# RS485.net
KiCad netlist of a schematic drawn in Altium Designer
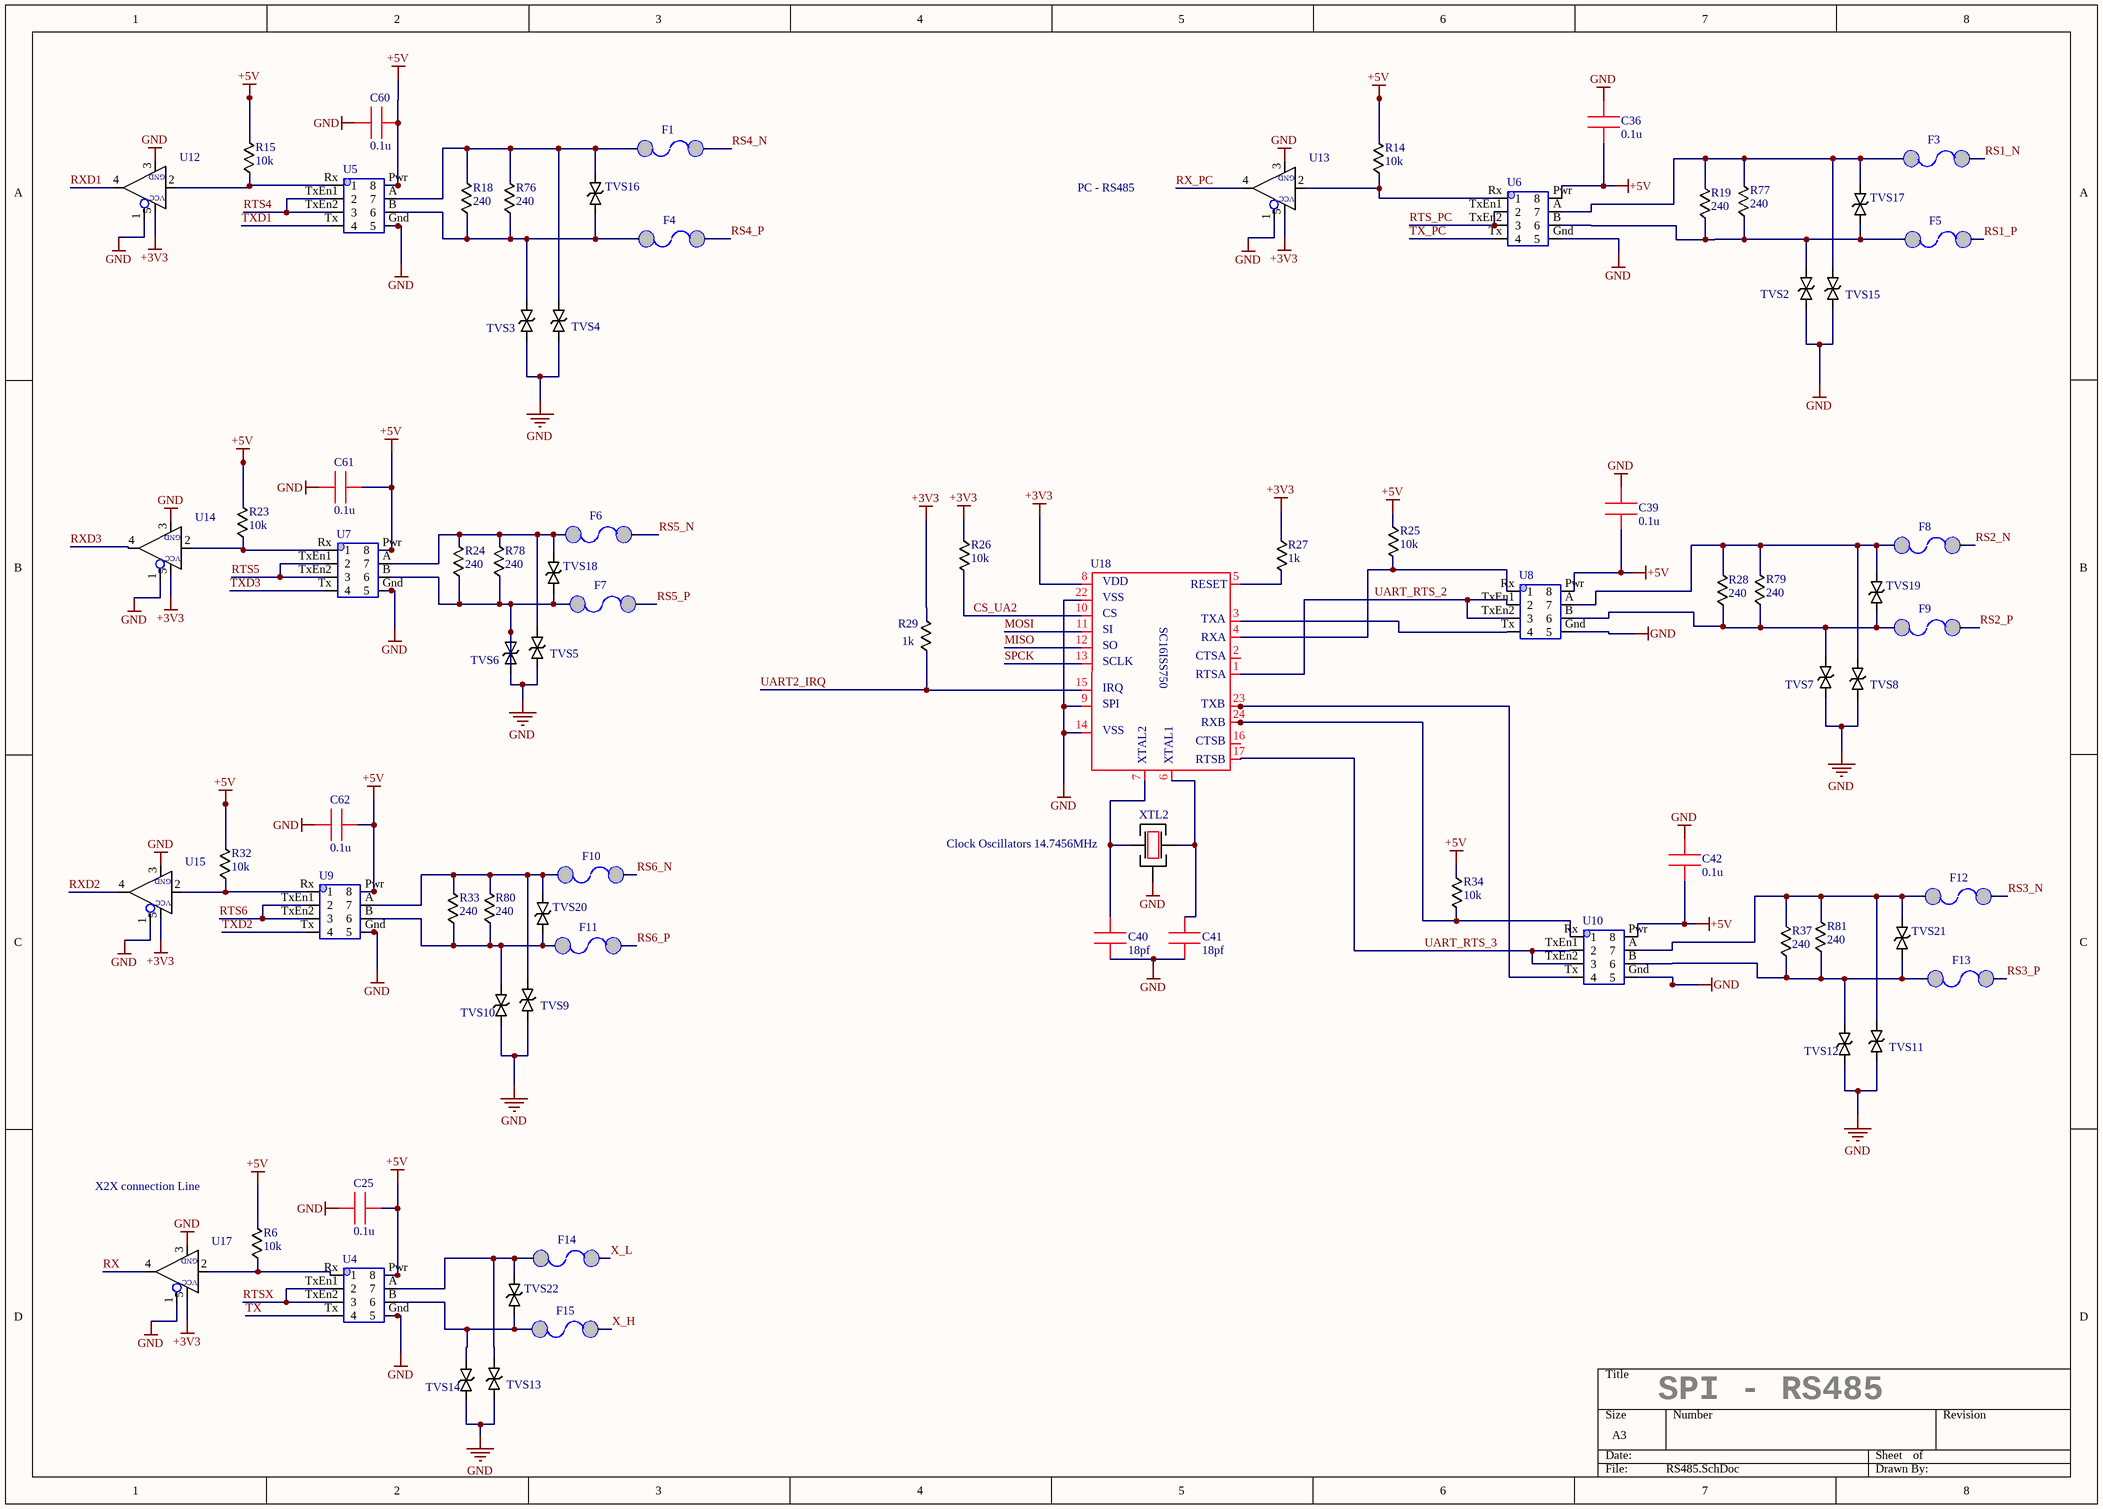
[diagram p0: RS485.SchDoc]

(export (version "E")
  (design (tool "Eeschema 10.0.6"))
  (components
    (comp (ref "C25")
      (value "0.1u")
      (footprint "0603")
      (fields (field (name "PART NUMBER") "GRM188R72A104KA35D"))
      (libsource (lib "kontr") (part "Capasitor 0805"))
    )
    (comp (ref "C36")
      (value "0.1u")
      (footprint "0603")
      (fields (field (name "PART NUMBER") "GRM188R72A104KA35D"))
      (libsource (lib "kontr") (part "Capasitor 0805"))
    )
    (comp (ref "C39")
      (value "0.1u")
      (footprint "0603")
      (fields (field (name "PART NUMBER") "GRM188R72A104KA35D"))
      (libsource (lib "kontr") (part "Capasitor 0805"))
    )
    (comp (ref "C40")
      (value "18pf")
      (footprint "0603")
      (fields (field (name "PART NUMBER") "GRM1885C1H180JA01D"))
      (libsource (lib "kontr") (part "Capasitor 0805"))
    )
    (comp (ref "C41")
      (value "18pf")
      (footprint "0603")
      (fields (field (name "PART NUMBER") "GRM1885C1H180JA01D"))
      (libsource (lib "kontr") (part "Capasitor 0805"))
    )
    (comp (ref "C42")
      (value "0.1u")
      (footprint "0603")
      (fields (field (name "PART NUMBER") "GRM188R72A104KA35D"))
      (libsource (lib "kontr") (part "Capasitor 0805"))
    )
    (comp (ref "C60")
      (value "0.1u")
      (footprint "0603")
      (fields (field (name "PART NUMBER") "GRM188R72A104KA35D"))
      (libsource (lib "kontr") (part "Capasitor 0805"))
    )
    (comp (ref "C61")
      (value "0.1u")
      (footprint "0603")
      (fields (field (name "PART NUMBER") "GRM188R72A104KA35D"))
      (libsource (lib "kontr") (part "Capasitor 0805"))
    )
    (comp (ref "C62")
      (value "0.1u")
      (footprint "0603")
      (fields (field (name "PART NUMBER") "GRM188R72A104KA35D"))
      (libsource (lib "kontr") (part "Capasitor 0805"))
    )
    (comp (ref "F1")
      (value "~")
      (footprint "1210")
      (fields (field (name "PART NUMBER") "MF-USMF005-2"))
      (libsource (lib "kontr") (part "Fuse PTS"))
    )
    (comp (ref "F3")
      (value "~")
      (footprint "1210")
      (fields (field (name "PART NUMBER") "MF-USMF005-2"))
      (libsource (lib "kontr") (part "Fuse PTS"))
    )
    (comp (ref "F4")
      (value "~")
      (footprint "1210")
      (fields (field (name "PART NUMBER") "MF-USMF005-2"))
      (libsource (lib "kontr") (part "Fuse PTS"))
    )
    (comp (ref "F5")
      (value "~")
      (footprint "1210")
      (fields (field (name "PART NUMBER") "MF-USMF005-2"))
      (libsource (lib "kontr") (part "Fuse PTS"))
    )
    (comp (ref "F6")
      (value "~")
      (footprint "1210")
      (fields (field (name "PART NUMBER") "MF-USMF005-2"))
      (libsource (lib "kontr") (part "Fuse PTS"))
    )
    (comp (ref "F7")
      (value "~")
      (footprint "1210")
      (fields (field (name "PART NUMBER") "MF-USMF005-2"))
      (libsource (lib "kontr") (part "Fuse PTS"))
    )
    (comp (ref "F8")
      (value "~")
      (footprint "1210")
      (fields (field (name "PART NUMBER") "MF-USMF005-2"))
      (libsource (lib "kontr") (part "Fuse PTS"))
    )
    (comp (ref "F9")
      (value "~")
      (footprint "1210")
      (fields (field (name "PART NUMBER") "MF-USMF005-2"))
      (libsource (lib "kontr") (part "Fuse PTS"))
    )
    (comp (ref "F10")
      (value "~")
      (footprint "1210")
      (fields (field (name "PART NUMBER") "MF-USMF005-2"))
      (libsource (lib "kontr") (part "Fuse PTS"))
    )
    (comp (ref "F11")
      (value "~")
      (footprint "1210")
      (fields (field (name "PART NUMBER") "MF-USMF005-2"))
      (libsource (lib "kontr") (part "Fuse PTS"))
    )
    (comp (ref "F12")
      (value "~")
      (footprint "1210")
      (fields (field (name "PART NUMBER") "MF-USMF005-2"))
      (libsource (lib "kontr") (part "Fuse PTS"))
    )
    (comp (ref "F13")
      (value "~")
      (footprint "1210")
      (fields (field (name "PART NUMBER") "MF-USMF005-2"))
      (libsource (lib "kontr") (part "Fuse PTS"))
    )
    (comp (ref "F14")
      (value "~")
      (footprint "1210")
      (fields (field (name "PART NUMBER") "MF-USMF005-2"))
      (libsource (lib "kontr") (part "Fuse PTS"))
    )
    (comp (ref "F15")
      (value "~")
      (footprint "1210")
      (fields (field (name "PART NUMBER") "MF-USMF005-2"))
      (libsource (lib "kontr") (part "Fuse PTS"))
    )
    (comp (ref "R6")
      (value "10k")
      (footprint "0603")
      (fields (field (name "PART NUMBER") "RC0603JR-0710K"))
      (libsource (lib "kontr") (part "Resistor 0805"))
    )
    (comp (ref "R14")
      (value "10k")
      (footprint "0603")
      (fields (field (name "PART NUMBER") "RC0603JR-0710K"))
      (libsource (lib "kontr") (part "Resistor 0805"))
    )
    (comp (ref "R15")
      (value "10k")
      (footprint "0603")
      (fields (field (name "PART NUMBER") "RC0603JR-0710K"))
      (libsource (lib "kontr") (part "Resistor 0805"))
    )
    (comp (ref "R18")
      (value "240")
      (footprint "0603")
      (fields (field (name "PART NUMBER") "RC0603FR-07240RL"))
      (libsource (lib "kontr") (part "Resistor 0805"))
    )
    (comp (ref "R19")
      (value "240")
      (footprint "0603")
      (fields (field (name "PART NUMBER") "RC0603FR-07240RL"))
      (libsource (lib "kontr") (part "Resistor 0805"))
    )
    (comp (ref "R23")
      (value "10k")
      (footprint "0603")
      (fields (field (name "PART NUMBER") "RC0603JR-0710K"))
      (libsource (lib "kontr") (part "Resistor 0805"))
    )
    (comp (ref "R24")
      (value "240")
      (footprint "0603")
      (fields (field (name "PART NUMBER") "RC0603FR-07240RL"))
      (libsource (lib "kontr") (part "Resistor 0805"))
    )
    (comp (ref "R25")
      (value "10k")
      (footprint "0603")
      (fields (field (name "PART NUMBER") "RC0603JR-0710K"))
      (libsource (lib "kontr") (part "Resistor 0805"))
    )
    (comp (ref "R26")
      (value "10k")
      (footprint "0603")
      (fields (field (name "PART NUMBER") "RC0603JR-0710K"))
      (libsource (lib "kontr") (part "Resistor 0805"))
    )
    (comp (ref "R27")
      (value "1k")
      (footprint "0603")
      (fields (field (name "PART NUMBER") "RC0603JR-071KL"))
      (libsource (lib "kontr") (part "Resistor 0805"))
    )
    (comp (ref "R28")
      (value "240")
      (footprint "0603")
      (fields (field (name "PART NUMBER") "RC0603FR-07240RL"))
      (libsource (lib "kontr") (part "Resistor 0805"))
    )
    (comp (ref "R29")
      (value "1k")
      (footprint "0603")
      (fields (field (name "PART NUMBER") "RC0603JR-071KL"))
      (libsource (lib "kontr") (part "Resistor 0805"))
    )
    (comp (ref "R32")
      (value "10k")
      (footprint "0603")
      (fields (field (name "PART NUMBER") "RC0603JR-0710K"))
      (libsource (lib "kontr") (part "Resistor 0805"))
    )
    (comp (ref "R33")
      (value "240")
      (footprint "0603")
      (fields (field (name "PART NUMBER") "RC0603FR-07240RL"))
      (libsource (lib "kontr") (part "Resistor 0805"))
    )
    (comp (ref "R34")
      (value "10k")
      (footprint "0603")
      (fields (field (name "PART NUMBER") "RC0603JR-0710K"))
      (libsource (lib "kontr") (part "Resistor 0805"))
    )
    (comp (ref "R37")
      (value "240")
      (footprint "0603")
      (fields (field (name "PART NUMBER") "RC0603FR-07240RL"))
      (libsource (lib "kontr") (part "Resistor 0805"))
    )
    (comp (ref "R76")
      (value "240")
      (footprint "0603")
      (fields (field (name "PART NUMBER") "RC0603FR-07240RL"))
      (libsource (lib "kontr") (part "Resistor 0805"))
    )
    (comp (ref "R77")
      (value "240")
      (footprint "0603")
      (fields (field (name "PART NUMBER") "RC0603FR-07240RL"))
      (libsource (lib "kontr") (part "Resistor 0805"))
    )
    (comp (ref "R78")
      (value "240")
      (footprint "0603")
      (fields (field (name "PART NUMBER") "RC0603FR-07240RL"))
      (libsource (lib "kontr") (part "Resistor 0805"))
    )
    (comp (ref "R79")
      (value "240")
      (footprint "0603")
      (fields (field (name "PART NUMBER") "RC0603FR-07240RL"))
      (libsource (lib "kontr") (part "Resistor 0805"))
    )
    (comp (ref "R80")
      (value "240")
      (footprint "0603")
      (fields (field (name "PART NUMBER") "RC0603FR-07240RL"))
      (libsource (lib "kontr") (part "Resistor 0805"))
    )
    (comp (ref "R81")
      (value "240")
      (footprint "0603")
      (fields (field (name "PART NUMBER") "RC0603FR-07240RL"))
      (libsource (lib "kontr") (part "Resistor 0805"))
    )
    (comp (ref "TVS2")
      (value "~")
      (footprint "DO-214AC")
      (fields (field (name "PART NUMBER") "SMAJ5.0CA"))
      (libsource (lib "kontr") (part "SMAJ5.0CA"))
    )
    (comp (ref "TVS3")
      (value "~")
      (footprint "DO-214AC")
      (fields (field (name "PART NUMBER") "SMAJ5.0CA"))
      (libsource (lib "kontr") (part "SMAJ5.0CA"))
    )
    (comp (ref "TVS4")
      (value "~")
      (footprint "DO-214AC")
      (fields (field (name "PART NUMBER") "SMAJ5.0CA"))
      (libsource (lib "kontr") (part "SMAJ5.0CA"))
    )
    (comp (ref "TVS5")
      (value "~")
      (footprint "DO-214AC")
      (fields (field (name "PART NUMBER") "SMAJ5.0CA"))
      (libsource (lib "kontr") (part "SMAJ5.0CA"))
    )
    (comp (ref "TVS6")
      (value "~")
      (footprint "DO-214AC")
      (fields (field (name "PART NUMBER") "SMAJ5.0CA"))
      (libsource (lib "kontr") (part "SMAJ5.0CA"))
    )
    (comp (ref "TVS7")
      (value "~")
      (footprint "DO-214AC")
      (fields (field (name "PART NUMBER") "SMAJ5.0CA"))
      (libsource (lib "kontr") (part "SMAJ5.0CA"))
    )
    (comp (ref "TVS8")
      (value "~")
      (footprint "DO-214AC")
      (fields (field (name "PART NUMBER") "SMAJ5.0CA"))
      (libsource (lib "kontr") (part "SMAJ5.0CA"))
    )
    (comp (ref "TVS9")
      (value "~")
      (footprint "DO-214AC")
      (fields (field (name "PART NUMBER") "SMAJ5.0CA"))
      (libsource (lib "kontr") (part "SMAJ5.0CA"))
    )
    (comp (ref "TVS10")
      (value "~")
      (footprint "DO-214AC")
      (fields (field (name "PART NUMBER") "SMAJ5.0CA"))
      (libsource (lib "kontr") (part "SMAJ5.0CA"))
    )
    (comp (ref "TVS11")
      (value "~")
      (footprint "DO-214AC")
      (fields (field (name "PART NUMBER") "SMAJ5.0CA"))
      (libsource (lib "kontr") (part "SMAJ5.0CA"))
    )
    (comp (ref "TVS12")
      (value "~")
      (footprint "DO-214AC")
      (fields (field (name "PART NUMBER") "SMAJ5.0CA"))
      (libsource (lib "kontr") (part "SMAJ5.0CA"))
    )
    (comp (ref "TVS13")
      (value "~")
      (footprint "DO-214AC")
      (fields (field (name "PART NUMBER") "SMAJ5.0CA"))
      (libsource (lib "kontr") (part "SMAJ5.0CA"))
    )
    (comp (ref "TVS14")
      (value "~")
      (footprint "DO-214AC")
      (fields (field (name "PART NUMBER") "SMAJ5.0CA"))
      (libsource (lib "kontr") (part "SMAJ5.0CA"))
    )
    (comp (ref "TVS15")
      (value "~")
      (footprint "DO-214AC")
      (fields (field (name "PART NUMBER") "SMAJ5.0CA"))
      (libsource (lib "kontr") (part "SMAJ5.0CA"))
    )
    (comp (ref "TVS16")
      (value "~")
      (footprint "DO-214AC")
      (fields (field (name "PART NUMBER") "SMAJ5.0CA"))
      (libsource (lib "kontr") (part "TVS"))
    )
    (comp (ref "TVS17")
      (value "~")
      (footprint "DO-214AC")
      (fields (field (name "PART NUMBER") "SMAJ5.0CA"))
      (libsource (lib "kontr") (part "TVS"))
    )
    (comp (ref "TVS18")
      (value "~")
      (footprint "DO-214AC")
      (fields (field (name "PART NUMBER") "SMAJ5.0CA"))
      (libsource (lib "kontr") (part "TVS"))
    )
    (comp (ref "TVS19")
      (value "~")
      (footprint "DO-214AC")
      (fields (field (name "PART NUMBER") "SMAJ5.0CA"))
      (libsource (lib "kontr") (part "TVS"))
    )
    (comp (ref "TVS20")
      (value "~")
      (footprint "DO-214AC")
      (fields (field (name "PART NUMBER") "SMAJ5.0CA"))
      (libsource (lib "kontr") (part "TVS"))
    )
    (comp (ref "TVS21")
      (value "~")
      (footprint "DO-214AC")
      (fields (field (name "PART NUMBER") "SMAJ5.0CA"))
      (libsource (lib "kontr") (part "TVS"))
    )
    (comp (ref "TVS22")
      (value "~")
      (footprint "DO-214AC")
      (fields (field (name "PART NUMBER") "SMAJ5.0CA"))
      (libsource (lib "kontr") (part "TVS"))
    )
    (comp (ref "U4")
      (value "~")
      (footprint "MAX485 - duplicate")
      (fields (field (name "PART NUMBER") "SN65HVD3082EDR"))
      (libsource (lib "Schlib1") (part "MAX485"))
    )
    (comp (ref "U5")
      (value "~")
      (footprint "MAX485 - duplicate")
      (fields (field (name "PART NUMBER") "SN65HVD3082EDR"))
      (libsource (lib "Schlib1") (part "MAX485"))
    )
    (comp (ref "U6")
      (value "~")
      (footprint "MAX485 - duplicate")
      (fields (field (name "PART NUMBER") "SN65HVD3082EDR"))
      (libsource (lib "Schlib1") (part "MAX485"))
    )
    (comp (ref "U7")
      (value "~")
      (footprint "MAX485 - duplicate")
      (fields (field (name "PART NUMBER") "SN65HVD3082EDR"))
      (libsource (lib "Schlib1") (part "MAX485"))
    )
    (comp (ref "U8")
      (value "~")
      (footprint "MAX485 - duplicate")
      (fields (field (name "PART NUMBER") "SN65HVD3082EDR"))
      (libsource (lib "Schlib1") (part "MAX485"))
    )
    (comp (ref "U9")
      (value "~")
      (footprint "MAX485 - duplicate")
      (fields (field (name "PART NUMBER") "SN65HVD3082EDR"))
      (libsource (lib "Schlib1") (part "MAX485"))
    )
    (comp (ref "U10")
      (value "~")
      (footprint "MAX485 - duplicate")
      (fields (field (name "PART NUMBER") "SN65HVD3082EDR"))
      (libsource (lib "Schlib1") (part "MAX485"))
    )
    (comp (ref "U12")
      (value "~")
      (footprint "SOT23 - 5 lead")
      (fields (field (name "PART NUMBER") "SN74LVC1G125DBVR"))
      (libsource (lib "kontr") (part "Gate"))
    )
    (comp (ref "U13")
      (value "~")
      (footprint "SOT23 - 5 lead")
      (fields (field (name "PART NUMBER") "SN74LVC1G125DBVR"))
      (libsource (lib "kontr") (part "Gate"))
    )
    (comp (ref "U14")
      (value "~")
      (footprint "SOT23 - 5 lead")
      (fields (field (name "PART NUMBER") "SN74LVC1G125DBVR"))
      (libsource (lib "kontr") (part "Gate"))
    )
    (comp (ref "U15")
      (value "~")
      (footprint "SOT23 - 5 lead")
      (fields (field (name "PART NUMBER") "SN74LVC1G125DBVR"))
      (libsource (lib "kontr") (part "Gate"))
    )
    (comp (ref "U17")
      (value "~")
      (footprint "SOT23 - 5 lead")
      (fields (field (name "PART NUMBER") "SN74LVC1G125DBVR"))
      (libsource (lib "kontr") (part "Gate"))
    )
    (comp (ref "U18")
      (value "~")
      (footprint "TSSOP28")
      (fields (field (name "PART NUMBER") "SC16IS752IPW,128"))
      (libsource (lib "kontr") (part "SC16IS752"))
    )
    (comp (ref "XTL2")
      (value "~")
      (footprint "KX-7 XTAL")
      (fields
        (field (name "PART DESCRIPTION") "Clock Oscillators 14.7456MHz")
        (field (name "PART NUMBER") "Geyer KX-7 14.7456MHz")
      )
      (libsource (lib "kontr") (part "KX-7"))
    )
  )
  (nets
    (net (code "1") (name "+3V3") (class "Default")
      (node (ref "R26") (pin "1") (pintype "passive"))
      (node (ref "R27") (pin "1") (pintype "passive"))
      (node (ref "R29") (pin "2") (pintype "passive"))
      (node (ref "U12") (pin "5") (pinfunction "7_5") (pintype "passive"))
      (node (ref "U13") (pin "5") (pinfunction "7_5") (pintype "passive"))
      (node (ref "U14") (pin "5") (pinfunction "7_5") (pintype "passive"))
      (node (ref "U15") (pin "5") (pinfunction "7_5") (pintype "passive"))
      (node (ref "U17") (pin "5") (pinfunction "7_5") (pintype "passive"))
      (node (ref "U18") (pin "8") (pinfunction "8_8") (pintype "passive"))
    )
    (net (code "2") (name "+5V") (class "Default")
      (node (ref "C25") (pin "2") (pinfunction "2_2") (pintype "passive"))
      (node (ref "C36") (pin "2") (pinfunction "2_2") (pintype "passive"))
      (node (ref "C39") (pin "2") (pinfunction "2_2") (pintype "passive"))
      (node (ref "C42") (pin "2") (pinfunction "2_2") (pintype "passive"))
      (node (ref "C60") (pin "2") (pinfunction "2_2") (pintype "passive"))
      (node (ref "C61") (pin "2") (pinfunction "2_2") (pintype "passive"))
      (node (ref "C62") (pin "2") (pinfunction "2_2") (pintype "passive"))
      (node (ref "R14") (pin "2") (pintype "passive"))
      (node (ref "R15") (pin "2") (pintype "passive"))
      (node (ref "R23") (pin "2") (pintype "passive"))
      (node (ref "R25") (pin "1") (pintype "passive"))
      (node (ref "R32") (pin "2") (pintype "passive"))
      (node (ref "R34") (pin "1") (pintype "passive"))
      (node (ref "R6") (pin "2") (pintype "passive"))
      (node (ref "U10") (pin "Pwr") (pinfunction "8_Pwr") (pintype "passive"))
      (node (ref "U4") (pin "Pwr") (pinfunction "8_Pwr") (pintype "passive"))
      (node (ref "U5") (pin "Pwr") (pinfunction "8_Pwr") (pintype "passive"))
      (node (ref "U6") (pin "Pwr") (pinfunction "8_Pwr") (pintype "passive"))
      (node (ref "U7") (pin "Pwr") (pinfunction "8_Pwr") (pintype "passive"))
      (node (ref "U8") (pin "Pwr") (pinfunction "8_Pwr") (pintype "passive"))
      (node (ref "U9") (pin "Pwr") (pinfunction "8_Pwr") (pintype "passive"))
    )
    (net (code "3") (name "/CS_UA2") (class "Default")
      (node (ref "R26") (pin "2") (pintype "passive"))
      (node (ref "U18") (pin "10") (pinfunction "10_10") (pintype "passive"))
    )
    (net (code "4") (name "/MISO") (class "Default")
      (node (ref "U18") (pin "12") (pinfunction "12_12") (pintype "passive"))
    )
    (net (code "5") (name "/MOSI") (class "Default")
      (node (ref "U18") (pin "11") (pinfunction "11_11") (pintype "passive"))
    )
    (net (code "6") (name "/RS1_N") (class "Default")
      (node (ref "F3") (pin "1") (pinfunction "1_1") (pintype "passive"))
    )
    (net (code "7") (name "/RS1_P") (class "Default")
      (node (ref "F5") (pin "1") (pinfunction "1_1") (pintype "passive"))
    )
    (net (code "8") (name "/RS2_N") (class "Default")
      (node (ref "F8") (pin "1") (pinfunction "1_1") (pintype "passive"))
    )
    (net (code "9") (name "/RS2_P") (class "Default")
      (node (ref "F9") (pin "1") (pinfunction "1_1") (pintype "passive"))
    )
    (net (code "10") (name "/RS3_N") (class "Default")
      (node (ref "F12") (pin "1") (pinfunction "1_1") (pintype "passive"))
    )
    (net (code "11") (name "/RS3_P") (class "Default")
      (node (ref "F13") (pin "1") (pinfunction "1_1") (pintype "passive"))
    )
    (net (code "12") (name "/RS4_N") (class "Default")
      (node (ref "F1") (pin "1") (pinfunction "1_1") (pintype "passive"))
    )
    (net (code "13") (name "/RS4_P") (class "Default")
      (node (ref "F4") (pin "1") (pinfunction "1_1") (pintype "passive"))
    )
    (net (code "14") (name "/RS5_N") (class "Default")
      (node (ref "F6") (pin "1") (pinfunction "1_1") (pintype "passive"))
    )
    (net (code "15") (name "/RS5_P") (class "Default")
      (node (ref "F7") (pin "1") (pinfunction "1_1") (pintype "passive"))
    )
    (net (code "16") (name "/RS6_N") (class "Default")
      (node (ref "F10") (pin "1") (pinfunction "1_1") (pintype "passive"))
    )
    (net (code "17") (name "/RS6_P") (class "Default")
      (node (ref "F11") (pin "1") (pinfunction "1_1") (pintype "passive"))
    )
    (net (code "18") (name "/RTS4") (class "Default")
      (node (ref "U5") (pin "TxEn1") (pinfunction "2_TxEn1") (pintype "passive"))
      (node (ref "U5") (pin "TxEn2") (pinfunction "3_TxEn2") (pintype "passive"))
    )
    (net (code "19") (name "/RTS5") (class "Default")
      (node (ref "U7") (pin "TxEn1") (pinfunction "2_TxEn1") (pintype "passive"))
      (node (ref "U7") (pin "TxEn2") (pinfunction "3_TxEn2") (pintype "passive"))
    )
    (net (code "20") (name "/RTS6") (class "Default")
      (node (ref "U9") (pin "TxEn1") (pinfunction "2_TxEn1") (pintype "passive"))
      (node (ref "U9") (pin "TxEn2") (pinfunction "3_TxEn2") (pintype "passive"))
    )
    (net (code "21") (name "/RTSX") (class "Default")
      (node (ref "U4") (pin "TxEn1") (pinfunction "2_TxEn1") (pintype "passive"))
      (node (ref "U4") (pin "TxEn2") (pinfunction "3_TxEn2") (pintype "passive"))
    )
    (net (code "22") (name "/RTS_PC") (class "Default")
      (node (ref "U6") (pin "TxEn1") (pinfunction "2_TxEn1") (pintype "passive"))
      (node (ref "U6") (pin "TxEn2") (pinfunction "3_TxEn2") (pintype "passive"))
    )
    (net (code "23") (name "/RX") (class "Default")
      (node (ref "U17") (pin "4") (pinfunction "7_4") (pintype "passive"))
    )
    (net (code "24") (name "/RXD1") (class "Default")
      (node (ref "U12") (pin "4") (pinfunction "7_4") (pintype "passive"))
    )
    (net (code "25") (name "/RXD2") (class "Default")
      (node (ref "U15") (pin "4") (pinfunction "7_4") (pintype "passive"))
    )
    (net (code "26") (name "/RXD3") (class "Default")
      (node (ref "U14") (pin "4") (pinfunction "7_4") (pintype "passive"))
    )
    (net (code "27") (name "/RX_PC") (class "Default")
      (node (ref "U13") (pin "4") (pinfunction "7_4") (pintype "passive"))
    )
    (net (code "28") (name "/SPCK") (class "Default")
      (node (ref "U18") (pin "13") (pinfunction "13_13") (pintype "passive"))
    )
    (net (code "29") (name "/TX") (class "Default")
      (node (ref "U4") (pin "Tx") (pinfunction "4_Tx") (pintype "passive"))
    )
    (net (code "30") (name "/TXD1") (class "Default")
      (node (ref "U5") (pin "Tx") (pinfunction "4_Tx") (pintype "passive"))
    )
    (net (code "31") (name "/TXD2") (class "Default")
      (node (ref "U9") (pin "Tx") (pinfunction "4_Tx") (pintype "passive"))
    )
    (net (code "32") (name "/TXD3") (class "Default")
      (node (ref "U7") (pin "Tx") (pinfunction "4_Tx") (pintype "passive"))
    )
    (net (code "33") (name "/TX_PC") (class "Default")
      (node (ref "U6") (pin "Tx") (pinfunction "4_Tx") (pintype "passive"))
    )
    (net (code "34") (name "/UART2_IRQ") (class "Default")
      (node (ref "R29") (pin "1") (pintype "passive"))
      (node (ref "U18") (pin "15") (pinfunction "15_15") (pintype "passive"))
    )
    (net (code "35") (name "/UART_RTS_2") (class "Default")
      (node (ref "U18") (pin "1") (pinfunction "1_1") (pintype "passive"))
      (node (ref "U8") (pin "TxEn1") (pinfunction "2_TxEn1") (pintype "passive"))
      (node (ref "U8") (pin "TxEn2") (pinfunction "3_TxEn2") (pintype "passive"))
    )
    (net (code "36") (name "/UART_RTS_3") (class "Default")
      (node (ref "U10") (pin "TxEn1") (pinfunction "2_TxEn1") (pintype "passive"))
      (node (ref "U10") (pin "TxEn2") (pinfunction "3_TxEn2") (pintype "passive"))
      (node (ref "U18") (pin "17") (pinfunction "17_17") (pintype "passive"))
    )
    (net (code "37") (name "/X_H") (class "Default")
      (node (ref "F15") (pin "1") (pinfunction "1_1") (pintype "passive"))
    )
    (net (code "38") (name "/X_L") (class "Default")
      (node (ref "F14") (pin "1") (pinfunction "1_1") (pintype "passive"))
    )
    (net (code "39") (name "GND") (class "Default")
      (node (ref "C25") (pin "1") (pinfunction "1_1") (pintype "passive"))
      (node (ref "C36") (pin "1") (pinfunction "1_1") (pintype "passive"))
      (node (ref "C39") (pin "1") (pinfunction "1_1") (pintype "passive"))
      (node (ref "C40") (pin "1") (pinfunction "1_1") (pintype "passive"))
      (node (ref "C41") (pin "1") (pinfunction "1_1") (pintype "passive"))
      (node (ref "C42") (pin "1") (pinfunction "1_1") (pintype "passive"))
      (node (ref "C60") (pin "1") (pinfunction "1_1") (pintype "passive"))
      (node (ref "C61") (pin "1") (pinfunction "1_1") (pintype "passive"))
      (node (ref "C62") (pin "1") (pinfunction "1_1") (pintype "passive"))
      (node (ref "TVS10") (pin "1") (pinfunction "1_1") (pintype "passive"))
      (node (ref "TVS11") (pin "1") (pinfunction "1_1") (pintype "passive"))
      (node (ref "TVS12") (pin "1") (pinfunction "1_1") (pintype "passive"))
      (node (ref "TVS13") (pin "1") (pinfunction "1_1") (pintype "passive"))
      (node (ref "TVS14") (pin "1") (pinfunction "1_1") (pintype "passive"))
      (node (ref "TVS15") (pin "1") (pinfunction "1_1") (pintype "passive"))
      (node (ref "TVS2") (pin "1") (pinfunction "1_1") (pintype "passive"))
      (node (ref "TVS3") (pin "1") (pinfunction "1_1") (pintype "passive"))
      (node (ref "TVS4") (pin "1") (pinfunction "1_1") (pintype "passive"))
      (node (ref "TVS5") (pin "1") (pinfunction "1_1") (pintype "passive"))
      (node (ref "TVS6") (pin "1") (pinfunction "1_1") (pintype "passive"))
      (node (ref "TVS7") (pin "1") (pinfunction "1_1") (pintype "passive"))
      (node (ref "TVS8") (pin "1") (pinfunction "1_1") (pintype "passive"))
      (node (ref "TVS9") (pin "1") (pinfunction "1_1") (pintype "passive"))
      (node (ref "U10") (pin "Gnd") (pinfunction "5_Gnd") (pintype "passive"))
      (node (ref "U12") (pin "1") (pinfunction "7_1") (pintype "passive"))
      (node (ref "U12") (pin "3") (pinfunction "7_3") (pintype "passive"))
      (node (ref "U13") (pin "1") (pinfunction "7_1") (pintype "passive"))
      (node (ref "U13") (pin "3") (pinfunction "7_3") (pintype "passive"))
      (node (ref "U14") (pin "1") (pinfunction "7_1") (pintype "passive"))
      (node (ref "U14") (pin "3") (pinfunction "7_3") (pintype "passive"))
      (node (ref "U15") (pin "1") (pinfunction "7_1") (pintype "passive"))
      (node (ref "U15") (pin "3") (pinfunction "7_3") (pintype "passive"))
      (node (ref "U17") (pin "1") (pinfunction "7_1") (pintype "passive"))
      (node (ref "U17") (pin "3") (pinfunction "7_3") (pintype "passive"))
      (node (ref "U18") (pin "14") (pinfunction "14_14") (pintype "passive"))
      (node (ref "U18") (pin "22") (pinfunction "22_22") (pintype "passive"))
      (node (ref "U18") (pin "9") (pinfunction "9_9") (pintype "passive"))
      (node (ref "U4") (pin "Gnd") (pinfunction "5_Gnd") (pintype "passive"))
      (node (ref "U5") (pin "Gnd") (pinfunction "5_Gnd") (pintype "passive"))
      (node (ref "U6") (pin "Gnd") (pinfunction "5_Gnd") (pintype "passive"))
      (node (ref "U7") (pin "Gnd") (pinfunction "5_Gnd") (pintype "passive"))
      (node (ref "U8") (pin "Gnd") (pinfunction "5_Gnd") (pintype "passive"))
      (node (ref "U9") (pin "Gnd") (pinfunction "5_Gnd") (pintype "passive"))
      (node (ref "XTL2") (pin "2") (pinfunction "2_2") (pintype "passive"))
    )
    (net (code "40") (name "Net-(C40-Pad2)") (class "Default")
      (node (ref "C40") (pin "2") (pinfunction "2_2") (pintype "passive"))
      (node (ref "U18") (pin "7") (pinfunction "7_7") (pintype "passive"))
      (node (ref "XTL2") (pin "1") (pinfunction "5_1") (pintype "passive"))
    )
    (net (code "41") (name "Net-(C41-Pad2)") (class "Default")
      (node (ref "C41") (pin "2") (pinfunction "2_2") (pintype "passive"))
      (node (ref "U18") (pin "6") (pinfunction "6_6") (pintype "passive"))
      (node (ref "XTL2") (pin "3") (pinfunction "5_3") (pintype "passive"))
    )
    (net (code "42") (name "Net-(R27-Pad2)") (class "Default")
      (node (ref "R27") (pin "2") (pintype "passive"))
      (node (ref "U18") (pin "5") (pinfunction "5_5") (pintype "passive"))
    )
    (net (code "43") (name "Net-(U4-1)") (class "Default")
      (node (ref "R6") (pin "1") (pintype "passive"))
      (node (ref "U17") (pin "2") (pinfunction "7_2") (pintype "passive"))
      (node (ref "U4") (pin "Rx") (pinfunction "1_Rx") (pintype "passive"))
    )
    (net (code "44") (name "Net-(U4-6)") (class "Default")
      (node (ref "F15") (pin "2") (pinfunction "2_2") (pintype "passive"))
      (node (ref "TVS14") (pin "2") (pinfunction "2_2") (pintype "passive"))
      (node (ref "TVS22") (pin "1") (pinfunction "1_1") (pintype "passive"))
      (node (ref "U4") (pin "B") (pinfunction "6_B") (pintype "passive"))
    )
    (net (code "45") (name "Net-(U4-7)") (class "Default")
      (node (ref "F14") (pin "2") (pinfunction "2_2") (pintype "passive"))
      (node (ref "TVS13") (pin "2") (pinfunction "2_2") (pintype "passive"))
      (node (ref "TVS22") (pin "2") (pinfunction "2_2") (pintype "passive"))
      (node (ref "U4") (pin "A") (pinfunction "7_A") (pintype "passive"))
    )
    (net (code "46") (name "Net-(U5-1)") (class "Default")
      (node (ref "R15") (pin "1") (pintype "passive"))
      (node (ref "U12") (pin "2") (pinfunction "7_2") (pintype "passive"))
      (node (ref "U5") (pin "Rx") (pinfunction "1_Rx") (pintype "passive"))
    )
    (net (code "47") (name "Net-(U5-6)") (class "Default")
      (node (ref "F4") (pin "2") (pinfunction "2_2") (pintype "passive"))
      (node (ref "R18") (pin "1") (pintype "passive"))
      (node (ref "R76") (pin "1") (pintype "passive"))
      (node (ref "TVS16") (pin "1") (pinfunction "1_1") (pintype "passive"))
      (node (ref "TVS3") (pin "2") (pinfunction "2_2") (pintype "passive"))
      (node (ref "U5") (pin "B") (pinfunction "6_B") (pintype "passive"))
    )
    (net (code "48") (name "Net-(U5-7)") (class "Default")
      (node (ref "F1") (pin "2") (pinfunction "2_2") (pintype "passive"))
      (node (ref "R18") (pin "2") (pintype "passive"))
      (node (ref "R76") (pin "2") (pintype "passive"))
      (node (ref "TVS16") (pin "2") (pinfunction "2_2") (pintype "passive"))
      (node (ref "TVS4") (pin "2") (pinfunction "2_2") (pintype "passive"))
      (node (ref "U5") (pin "A") (pinfunction "7_A") (pintype "passive"))
    )
    (net (code "49") (name "Net-(U6-1)") (class "Default")
      (node (ref "R14") (pin "1") (pintype "passive"))
      (node (ref "U13") (pin "2") (pinfunction "7_2") (pintype "passive"))
      (node (ref "U6") (pin "Rx") (pinfunction "1_Rx") (pintype "passive"))
    )
    (net (code "50") (name "Net-(U6-6)") (class "Default")
      (node (ref "F5") (pin "2") (pinfunction "2_2") (pintype "passive"))
      (node (ref "R19") (pin "1") (pintype "passive"))
      (node (ref "R77") (pin "1") (pintype "passive"))
      (node (ref "TVS17") (pin "1") (pinfunction "1_1") (pintype "passive"))
      (node (ref "TVS2") (pin "2") (pinfunction "2_2") (pintype "passive"))
      (node (ref "U6") (pin "B") (pinfunction "6_B") (pintype "passive"))
    )
    (net (code "51") (name "Net-(U6-7)") (class "Default")
      (node (ref "F3") (pin "2") (pinfunction "2_2") (pintype "passive"))
      (node (ref "R19") (pin "2") (pintype "passive"))
      (node (ref "R77") (pin "2") (pintype "passive"))
      (node (ref "TVS15") (pin "2") (pinfunction "2_2") (pintype "passive"))
      (node (ref "TVS17") (pin "2") (pinfunction "2_2") (pintype "passive"))
      (node (ref "U6") (pin "A") (pinfunction "7_A") (pintype "passive"))
    )
    (net (code "52") (name "Net-(U7-1)") (class "Default")
      (node (ref "R23") (pin "1") (pintype "passive"))
      (node (ref "U14") (pin "2") (pinfunction "7_2") (pintype "passive"))
      (node (ref "U7") (pin "Rx") (pinfunction "1_Rx") (pintype "passive"))
    )
    (net (code "53") (name "Net-(U7-6)") (class "Default")
      (node (ref "F7") (pin "2") (pinfunction "2_2") (pintype "passive"))
      (node (ref "R24") (pin "1") (pintype "passive"))
      (node (ref "R78") (pin "1") (pintype "passive"))
      (node (ref "TVS18") (pin "1") (pinfunction "1_1") (pintype "passive"))
      (node (ref "TVS6") (pin "2") (pinfunction "2_2") (pintype "passive"))
      (node (ref "U7") (pin "B") (pinfunction "6_B") (pintype "passive"))
    )
    (net (code "54") (name "Net-(U7-7)") (class "Default")
      (node (ref "F6") (pin "2") (pinfunction "2_2") (pintype "passive"))
      (node (ref "R24") (pin "2") (pintype "passive"))
      (node (ref "R78") (pin "2") (pintype "passive"))
      (node (ref "TVS18") (pin "2") (pinfunction "2_2") (pintype "passive"))
      (node (ref "TVS5") (pin "2") (pinfunction "2_2") (pintype "passive"))
      (node (ref "U7") (pin "A") (pinfunction "7_A") (pintype "passive"))
    )
    (net (code "55") (name "Net-(U8-1)") (class "Default")
      (node (ref "R25") (pin "2") (pintype "passive"))
      (node (ref "U18") (pin "4") (pinfunction "4_4") (pintype "passive"))
      (node (ref "U8") (pin "Rx") (pinfunction "1_Rx") (pintype "passive"))
    )
    (net (code "56") (name "Net-(U8-4)") (class "Default")
      (node (ref "U18") (pin "3") (pinfunction "3_3") (pintype "passive"))
      (node (ref "U8") (pin "Tx") (pinfunction "4_Tx") (pintype "passive"))
    )
    (net (code "57") (name "Net-(U8-6)") (class "Default")
      (node (ref "F9") (pin "2") (pinfunction "2_2") (pintype "passive"))
      (node (ref "R28") (pin "1") (pintype "passive"))
      (node (ref "R79") (pin "1") (pintype "passive"))
      (node (ref "TVS19") (pin "1") (pinfunction "1_1") (pintype "passive"))
      (node (ref "TVS7") (pin "2") (pinfunction "2_2") (pintype "passive"))
      (node (ref "U8") (pin "B") (pinfunction "6_B") (pintype "passive"))
    )
    (net (code "58") (name "Net-(U8-7)") (class "Default")
      (node (ref "F8") (pin "2") (pinfunction "2_2") (pintype "passive"))
      (node (ref "R28") (pin "2") (pintype "passive"))
      (node (ref "R79") (pin "2") (pintype "passive"))
      (node (ref "TVS19") (pin "2") (pinfunction "2_2") (pintype "passive"))
      (node (ref "TVS8") (pin "2") (pinfunction "2_2") (pintype "passive"))
      (node (ref "U8") (pin "A") (pinfunction "7_A") (pintype "passive"))
    )
    (net (code "59") (name "Net-(U9-1)") (class "Default")
      (node (ref "R32") (pin "1") (pintype "passive"))
      (node (ref "U15") (pin "2") (pinfunction "7_2") (pintype "passive"))
      (node (ref "U9") (pin "Rx") (pinfunction "1_Rx") (pintype "passive"))
    )
    (net (code "60") (name "Net-(U9-6)") (class "Default")
      (node (ref "F11") (pin "2") (pinfunction "2_2") (pintype "passive"))
      (node (ref "R33") (pin "1") (pintype "passive"))
      (node (ref "R80") (pin "1") (pintype "passive"))
      (node (ref "TVS10") (pin "2") (pinfunction "2_2") (pintype "passive"))
      (node (ref "TVS20") (pin "1") (pinfunction "1_1") (pintype "passive"))
      (node (ref "U9") (pin "B") (pinfunction "6_B") (pintype "passive"))
    )
    (net (code "61") (name "Net-(U9-7)") (class "Default")
      (node (ref "F10") (pin "2") (pinfunction "2_2") (pintype "passive"))
      (node (ref "R33") (pin "2") (pintype "passive"))
      (node (ref "R80") (pin "2") (pintype "passive"))
      (node (ref "TVS20") (pin "2") (pinfunction "2_2") (pintype "passive"))
      (node (ref "TVS9") (pin "2") (pinfunction "2_2") (pintype "passive"))
      (node (ref "U9") (pin "A") (pinfunction "7_A") (pintype "passive"))
    )
    (net (code "62") (name "Net-(U10-1)") (class "Default")
      (node (ref "R34") (pin "2") (pintype "passive"))
      (node (ref "U10") (pin "Rx") (pinfunction "1_Rx") (pintype "passive"))
      (node (ref "U18") (pin "24") (pinfunction "24_24") (pintype "passive"))
    )
    (net (code "63") (name "Net-(U10-4)") (class "Default")
      (node (ref "U10") (pin "Tx") (pinfunction "4_Tx") (pintype "passive"))
      (node (ref "U18") (pin "23") (pinfunction "23_23") (pintype "passive"))
    )
    (net (code "64") (name "Net-(U10-6)") (class "Default")
      (node (ref "F13") (pin "2") (pinfunction "2_2") (pintype "passive"))
      (node (ref "R37") (pin "1") (pintype "passive"))
      (node (ref "R81") (pin "1") (pintype "passive"))
      (node (ref "TVS12") (pin "2") (pinfunction "2_2") (pintype "passive"))
      (node (ref "TVS21") (pin "1") (pinfunction "1_1") (pintype "passive"))
      (node (ref "U10") (pin "B") (pinfunction "6_B") (pintype "passive"))
    )
    (net (code "65") (name "Net-(U10-7)") (class "Default")
      (node (ref "F12") (pin "2") (pinfunction "2_2") (pintype "passive"))
      (node (ref "R37") (pin "2") (pintype "passive"))
      (node (ref "R81") (pin "2") (pintype "passive"))
      (node (ref "TVS11") (pin "2") (pinfunction "2_2") (pintype "passive"))
      (node (ref "TVS21") (pin "2") (pinfunction "2_2") (pintype "passive"))
      (node (ref "U10") (pin "A") (pinfunction "7_A") (pintype "passive"))
    )
    (net (code "66") (name "unconnected-(U18-Pad2)") (class "Default")
      (node (ref "U18") (pin "2") (pinfunction "2_2") (pintype "passive"))
    )
    (net (code "67") (name "unconnected-(U18-Pad16)") (class "Default")
      (node (ref "U18") (pin "16") (pinfunction "16_16") (pintype "passive"))
    )
  )
)
